# decoupling.net
KiCad netlist of a schematic drawn in EAGLE
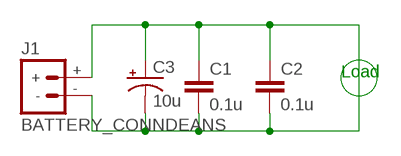
[diagram p0: schematic, sheet 1]

(export (version "E")
  (design (tool "Eeschema 10.0.6"))
  (components
    (comp (ref "C1")
      (value "0.1u")
      (footprint "eagle-import:CAP-PTH-SMALL")
      (libsource (lib "eagle-import") (part "CAPPTH"))
    )
    (comp (ref "C2")
      (value "0.1u")
      (footprint "eagle-import:CAP-PTH-SMALL")
      (libsource (lib "eagle-import") (part "CAPPTH"))
    )
    (comp (ref "C3")
      (value "10u")
      (footprint "eagle-import:CPOL-RADIAL-10UF-25V")
      (libsource (lib "eagle-import") (part "CAP_POLPTH2"))
    )
    (comp (ref "J1")
      (value "BATTERY_CONNDEANS")
      (footprint "eagle-import:DEANS")
      (libsource (lib "eagle-import") (part "BATTERY_CONNDEANS"))
    )
  )
  (nets
    (net (code "1") (name "Net-(C3-+)") (class "Default")
      (node (ref "C1") (pin "1") (pinfunction "1_1") (pintype "passive"))
      (node (ref "C1") (pin "2") (pinfunction "2_2") (pintype "passive"))
      (node (ref "C2") (pin "1") (pinfunction "1_1") (pintype "passive"))
      (node (ref "C2") (pin "2") (pinfunction "2_2") (pintype "passive"))
      (node (ref "C3") (pin "1") (pinfunction "+_1") (pintype "passive"))
      (node (ref "C3") (pin "2") (pinfunction "-_2") (pintype "passive"))
      (node (ref "J1") (pin "+") (pinfunction "+_+") (pintype "passive"))
      (node (ref "J1") (pin "-") (pinfunction "-_-") (pintype "passive"))
    )
  )
)
